# Arduino.net
KiCad netlist of a schematic drawn in EAGLE
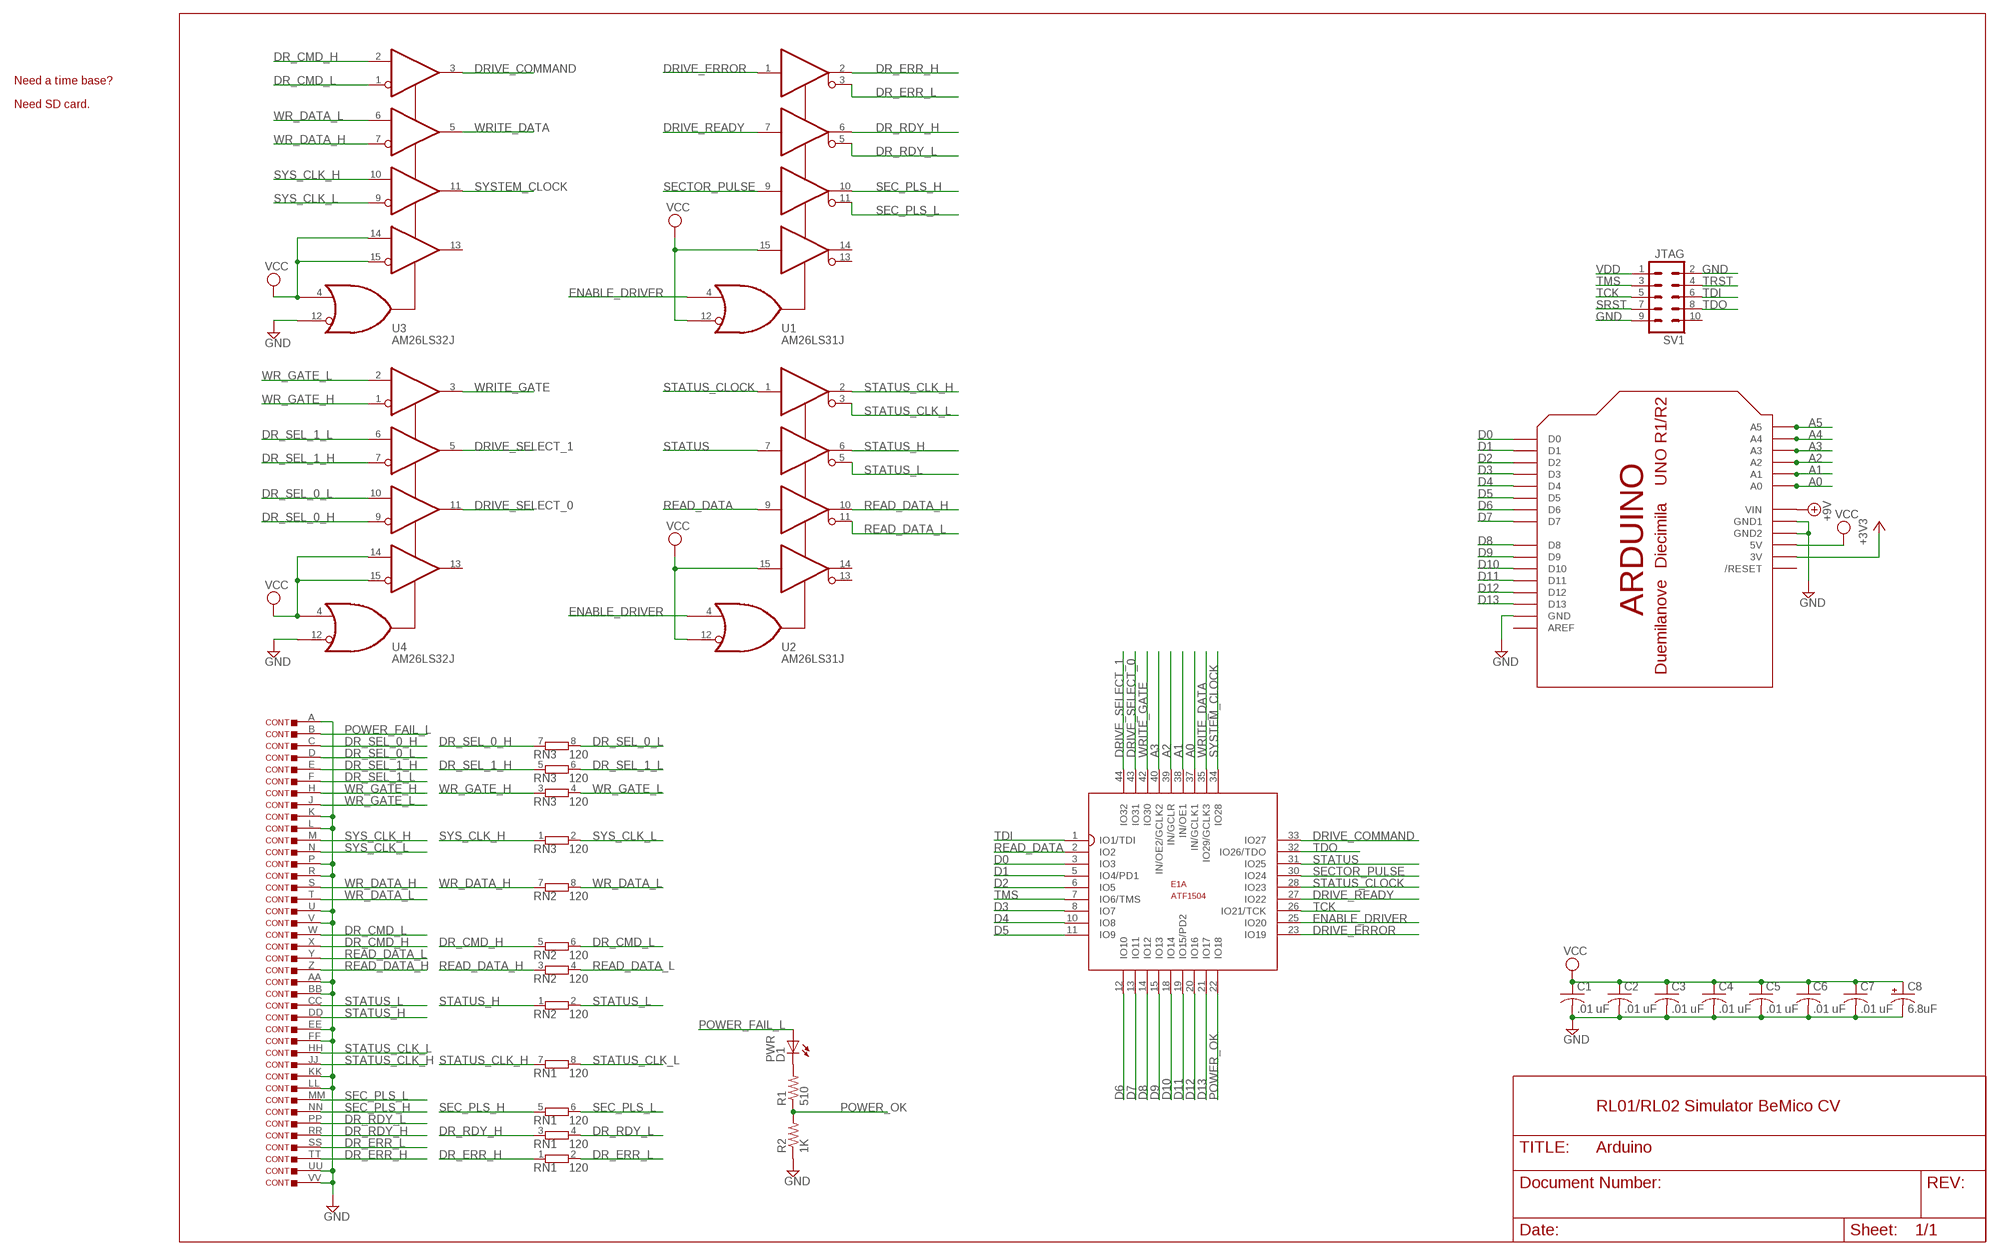
[diagram p0: schematic, sheet 1]

(export (version "E")
  (design (tool "Eeschema 10.0.6"))
  (components
    (comp (ref "C1")
      (value ".01 uF")
      (footprint "eagle-import:C050-025X075")
      (libsource (lib "eagle-import") (part "C-US050-025X075"))
    )
    (comp (ref "C2")
      (value ".01 uF")
      (footprint "eagle-import:C050-025X075")
      (libsource (lib "eagle-import") (part "C-US050-025X075"))
    )
    (comp (ref "C3")
      (value ".01 uF")
      (footprint "eagle-import:C050-025X075")
      (libsource (lib "eagle-import") (part "C-US050-025X075"))
    )
    (comp (ref "C4")
      (value ".01 uF")
      (footprint "eagle-import:C050-025X075")
      (libsource (lib "eagle-import") (part "C-US050-025X075"))
    )
    (comp (ref "C5")
      (value ".01 uF")
      (footprint "eagle-import:C050-025X075")
      (libsource (lib "eagle-import") (part "C-US050-025X075"))
    )
    (comp (ref "C6")
      (value ".01 uF")
      (footprint "eagle-import:C050-025X075")
      (libsource (lib "eagle-import") (part "C-US050-025X075"))
    )
    (comp (ref "C7")
      (value ".01 uF")
      (footprint "eagle-import:C050-025X075")
      (libsource (lib "eagle-import") (part "C-US050-025X075"))
    )
    (comp (ref "C8")
      (value "6.8uF")
      (footprint "eagle-import:E5-5")
      (libsource (lib "eagle-import") (part "CPOL-USE5-5"))
    )
    (comp (ref "CONT")
      (value "DEC40PINSV")
      (footprint "eagle-import:DEC40PINV")
      (libsource (lib "eagle-import") (part "DEC40PINSV"))
    )
    (comp (ref "D1")
      (value "PWR")
      (footprint "eagle-import:LED5MM")
      (libsource (lib "eagle-import") (part "LED5MM"))
    )
    (comp (ref "E1")
      (value "ATF1504")
      (footprint "eagle-import:TQFP44")
      (libsource (lib "eagle-import") (part "ATF150X44TQFP"))
    )
    (comp (ref "R1")
      (value "510")
      (footprint "eagle-import:0207_10")
      (libsource (lib "eagle-import") (part "R-US_0207/10"))
    )
    (comp (ref "R2")
      (value "1K")
      (footprint "eagle-import:0207_10")
      (libsource (lib "eagle-import") (part "R-US_0207/10"))
    )
    (comp (ref "RN1")
      (value "120")
      (footprint "eagle-import:SIL8")
      (libsource (lib "eagle-import") (part "E4RP"))
    )
    (comp (ref "RN2")
      (value "120")
      (footprint "eagle-import:SIL8")
      (libsource (lib "eagle-import") (part "E4RP"))
    )
    (comp (ref "RN3")
      (value "120")
      (footprint "eagle-import:SIL8")
      (libsource (lib "eagle-import") (part "E4RP"))
    )
    (comp (ref "SV1")
      (value "JTAG")
      (footprint "eagle-import:ML10")
      (libsource (lib "eagle-import") (part "ML10"))
    )
    (comp (ref "U$3")
      (value "ARDUINOUNO")
      (footprint "eagle-import:ARDUINO")
      (libsource (lib "eagle-import") (part "ARDUINOUNO"))
    )
    (comp (ref "U1")
      (value "AM26LS31J")
      (footprint "eagle-import:SO16")
      (libsource (lib "eagle-import") (part "AM26LS31J"))
    )
    (comp (ref "U2")
      (value "AM26LS31J")
      (footprint "eagle-import:SO16")
      (libsource (lib "eagle-import") (part "AM26LS31J"))
    )
    (comp (ref "U3")
      (value "AM26LS32J")
      (footprint "eagle-import:SO16")
      (libsource (lib "eagle-import") (part "AM26LS32J"))
    )
    (comp (ref "U4")
      (value "AM26LS32J")
      (footprint "eagle-import:SO16")
      (libsource (lib "eagle-import") (part "AM26LS32J"))
    )
  )
  (nets
    (net (code "1") (name "+3V3") (class "Default")
      (node (ref "U$3") (pin "3V") (pinfunction "3V_3V") (pintype "power_in"))
    )
    (net (code "2") (name "+9V") (class "Default")
      (node (ref "U$3") (pin "VIN") (pinfunction "VIN_VIN") (pintype "power_in"))
    )
    (net (code "3") (name "/A0") (class "Default")
      (node (ref "E1") (pin "37") (pinfunction "IN/GCLK1_37") (pintype "input"))
      (node (ref "U$3") (pin "A0") (pinfunction "A0_A0") (pintype "bidirectional"))
    )
    (net (code "4") (name "/A1") (class "Default")
      (node (ref "E1") (pin "38") (pinfunction "IN/OE1_38") (pintype "input"))
      (node (ref "U$3") (pin "A1") (pinfunction "A1_A1") (pintype "bidirectional"))
    )
    (net (code "5") (name "/A2") (class "Default")
      (node (ref "E1") (pin "39") (pinfunction "IN/GCLR_39") (pintype "input"))
      (node (ref "U$3") (pin "A2") (pinfunction "A2_A2") (pintype "bidirectional"))
    )
    (net (code "6") (name "/A3") (class "Default")
      (node (ref "E1") (pin "40") (pinfunction "IN/OE2/GCLK2_40") (pintype "input"))
      (node (ref "U$3") (pin "A3") (pinfunction "A3_A3") (pintype "bidirectional"))
    )
    (net (code "7") (name "/A4") (class "Default")
      (node (ref "U$3") (pin "A4") (pinfunction "A4_A4") (pintype "bidirectional"))
    )
    (net (code "8") (name "/A5") (class "Default")
      (node (ref "U$3") (pin "A5") (pinfunction "A5_A5") (pintype "bidirectional"))
    )
    (net (code "9") (name "/D0") (class "Default")
      (node (ref "E1") (pin "3") (pinfunction "IO3_3") (pintype "bidirectional"))
      (node (ref "U$3") (pin "D0") (pinfunction "D0_D0") (pintype "bidirectional"))
    )
    (net (code "10") (name "/D1") (class "Default")
      (node (ref "E1") (pin "5") (pinfunction "IO4/PD1_5") (pintype "bidirectional"))
      (node (ref "U$3") (pin "D1") (pinfunction "D1_D1") (pintype "bidirectional"))
    )
    (net (code "11") (name "/D2") (class "Default")
      (node (ref "E1") (pin "6") (pinfunction "IO5_6") (pintype "bidirectional"))
      (node (ref "U$3") (pin "D2") (pinfunction "D2_D2") (pintype "bidirectional"))
    )
    (net (code "12") (name "/D3") (class "Default")
      (node (ref "E1") (pin "8") (pinfunction "IO7_8") (pintype "bidirectional"))
      (node (ref "U$3") (pin "D3") (pinfunction "D3_D3") (pintype "bidirectional"))
    )
    (net (code "13") (name "/D4") (class "Default")
      (node (ref "E1") (pin "10") (pinfunction "IO8_10") (pintype "bidirectional"))
      (node (ref "U$3") (pin "D4") (pinfunction "D4_D4") (pintype "bidirectional"))
    )
    (net (code "14") (name "/D5") (class "Default")
      (node (ref "E1") (pin "11") (pinfunction "IO9_11") (pintype "bidirectional"))
      (node (ref "U$3") (pin "D5") (pinfunction "D5_D5") (pintype "bidirectional"))
    )
    (net (code "15") (name "/D6") (class "Default")
      (node (ref "E1") (pin "12") (pinfunction "IO10_12") (pintype "bidirectional"))
      (node (ref "U$3") (pin "D6") (pinfunction "D6_D6") (pintype "bidirectional"))
    )
    (net (code "16") (name "/D7") (class "Default")
      (node (ref "E1") (pin "13") (pinfunction "IO11_13") (pintype "bidirectional"))
      (node (ref "U$3") (pin "D7") (pinfunction "D7_D7") (pintype "bidirectional"))
    )
    (net (code "17") (name "/D8") (class "Default")
      (node (ref "E1") (pin "14") (pinfunction "IO12_14") (pintype "bidirectional"))
      (node (ref "U$3") (pin "D8") (pinfunction "D8_D8") (pintype "bidirectional"))
    )
    (net (code "18") (name "/D9") (class "Default")
      (node (ref "E1") (pin "15") (pinfunction "IO13_15") (pintype "bidirectional"))
      (node (ref "U$3") (pin "D9") (pinfunction "D9_D9") (pintype "bidirectional"))
    )
    (net (code "19") (name "/D10") (class "Default")
      (node (ref "E1") (pin "18") (pinfunction "IO14_18") (pintype "bidirectional"))
      (node (ref "U$3") (pin "D10") (pinfunction "D10_D10") (pintype "bidirectional"))
    )
    (net (code "20") (name "/D11") (class "Default")
      (node (ref "E1") (pin "19") (pinfunction "IO15/PD2_19") (pintype "bidirectional"))
      (node (ref "U$3") (pin "D11") (pinfunction "D11_D11") (pintype "bidirectional"))
    )
    (net (code "21") (name "/D12") (class "Default")
      (node (ref "E1") (pin "20") (pinfunction "IO16_20") (pintype "bidirectional"))
      (node (ref "U$3") (pin "D12") (pinfunction "D12_D12") (pintype "bidirectional"))
    )
    (net (code "22") (name "/D13") (class "Default")
      (node (ref "E1") (pin "21") (pinfunction "IO17_21") (pintype "bidirectional"))
      (node (ref "U$3") (pin "D13") (pinfunction "D13_D13") (pintype "bidirectional"))
    )
    (net (code "23") (name "/DRIVE_COMMAND") (class "Default")
      (node (ref "E1") (pin "33") (pinfunction "IO27_33") (pintype "bidirectional"))
      (node (ref "U3") (pin "3") (pinfunction "Y1_3") (pintype "output"))
    )
    (net (code "24") (name "/DRIVE_ERROR") (class "Default")
      (node (ref "E1") (pin "23") (pinfunction "IO19_23") (pintype "bidirectional"))
      (node (ref "U1") (pin "1") (pinfunction "A1_1") (pintype "input"))
    )
    (net (code "25") (name "/DRIVE_READY") (class "Default")
      (node (ref "E1") (pin "27") (pinfunction "IO22_27") (pintype "bidirectional"))
      (node (ref "U1") (pin "7") (pinfunction "A2_7") (pintype "input"))
    )
    (net (code "26") (name "/DRIVE_SELECT_0") (class "Default")
      (node (ref "E1") (pin "43") (pinfunction "IO31_43") (pintype "bidirectional"))
      (node (ref "U4") (pin "11") (pinfunction "Y3_11") (pintype "output"))
    )
    (net (code "27") (name "/DRIVE_SELECT_1") (class "Default")
      (node (ref "E1") (pin "44") (pinfunction "IO32_44") (pintype "bidirectional"))
      (node (ref "U4") (pin "5") (pinfunction "Y2_5") (pintype "output"))
    )
    (net (code "28") (name "/DR_CMD_H") (class "Default")
      (node (ref "CONT") (pin "X") (pinfunction "P$2_X") (pintype "passive"))
      (node (ref "RN2") (pin "5") (pinfunction "1_5") (pintype "passive"))
      (node (ref "U3") (pin "2") (pinfunction "P1_2") (pintype "input"))
    )
    (net (code "29") (name "/DR_CMD_L") (class "Default")
      (node (ref "CONT") (pin "W") (pinfunction "P$2_W") (pintype "passive"))
      (node (ref "RN2") (pin "6") (pinfunction "2_6") (pintype "passive"))
      (node (ref "U3") (pin "1") (pinfunction "N1_1") (pintype "input"))
    )
    (net (code "30") (name "/DR_ERR_H") (class "Default")
      (node (ref "CONT") (pin "TT") (pinfunction "P$2_TT") (pintype "passive"))
      (node (ref "RN1") (pin "1") (pinfunction "1_1") (pintype "passive"))
      (node (ref "U1") (pin "2") (pinfunction "Y1_2") (pintype "output"))
    )
    (net (code "31") (name "/DR_ERR_L") (class "Default")
      (node (ref "CONT") (pin "SS") (pinfunction "P$2_SS") (pintype "passive"))
      (node (ref "RN1") (pin "2") (pinfunction "2_2") (pintype "passive"))
      (node (ref "U1") (pin "3") (pinfunction "Z1_3") (pintype "output"))
    )
    (net (code "32") (name "/DR_RDY_H") (class "Default")
      (node (ref "CONT") (pin "RR") (pinfunction "P$2_RR") (pintype "passive"))
      (node (ref "RN1") (pin "3") (pinfunction "1_3") (pintype "passive"))
      (node (ref "U1") (pin "6") (pinfunction "Y2_6") (pintype "output"))
    )
    (net (code "33") (name "/DR_RDY_L") (class "Default")
      (node (ref "CONT") (pin "PP") (pinfunction "P$2_PP") (pintype "passive"))
      (node (ref "RN1") (pin "4") (pinfunction "2_4") (pintype "passive"))
      (node (ref "U1") (pin "5") (pinfunction "Z2_5") (pintype "output"))
    )
    (net (code "34") (name "/DR_SEL_0_H") (class "Default")
      (node (ref "CONT") (pin "C") (pinfunction "P$2_C") (pintype "passive"))
      (node (ref "RN3") (pin "7") (pinfunction "1_7") (pintype "passive"))
      (node (ref "U4") (pin "9") (pinfunction "N3_9") (pintype "input"))
    )
    (net (code "35") (name "/DR_SEL_0_L") (class "Default")
      (node (ref "CONT") (pin "D") (pinfunction "P$2_D") (pintype "passive"))
      (node (ref "RN3") (pin "8") (pinfunction "2_8") (pintype "passive"))
      (node (ref "U4") (pin "10") (pinfunction "P3_10") (pintype "input"))
    )
    (net (code "36") (name "/DR_SEL_1_H") (class "Default")
      (node (ref "CONT") (pin "E") (pinfunction "P$2_E") (pintype "passive"))
      (node (ref "RN3") (pin "5") (pinfunction "1_5") (pintype "passive"))
      (node (ref "U4") (pin "7") (pinfunction "N2_7") (pintype "input"))
    )
    (net (code "37") (name "/DR_SEL_1_L") (class "Default")
      (node (ref "CONT") (pin "F") (pinfunction "P$2_F") (pintype "passive"))
      (node (ref "RN3") (pin "6") (pinfunction "2_6") (pintype "passive"))
      (node (ref "U4") (pin "6") (pinfunction "P2_6") (pintype "input"))
    )
    (net (code "38") (name "/ENABLE_DRIVER") (class "Default")
      (node (ref "E1") (pin "25") (pinfunction "IO20_25") (pintype "bidirectional"))
      (node (ref "U1") (pin "4") (pinfunction "G_4") (pintype "input"))
      (node (ref "U2") (pin "4") (pinfunction "G_4") (pintype "input"))
    )
    (net (code "39") (name "/POWER_FAIL_L") (class "Default")
      (node (ref "CONT") (pin "B") (pinfunction "P$2_B") (pintype "passive"))
      (node (ref "D1") (pin "A") (pinfunction "A_A") (pintype "passive"))
    )
    (net (code "40") (name "/POWER_OK") (class "Default")
      (node (ref "E1") (pin "22") (pinfunction "IO18_22") (pintype "bidirectional"))
      (node (ref "R1") (pin "1") (pinfunction "1_1") (pintype "passive"))
      (node (ref "R2") (pin "2") (pinfunction "2_2") (pintype "passive"))
    )
    (net (code "41") (name "/READ_DATA") (class "Default")
      (node (ref "E1") (pin "2") (pinfunction "IO2_2") (pintype "bidirectional"))
      (node (ref "U2") (pin "9") (pinfunction "A3_9") (pintype "input"))
    )
    (net (code "42") (name "/READ_DATA_H") (class "Default")
      (node (ref "CONT") (pin "Z") (pinfunction "P$2_Z") (pintype "passive"))
      (node (ref "RN2") (pin "3") (pinfunction "1_3") (pintype "passive"))
      (node (ref "U2") (pin "10") (pinfunction "Y3_10") (pintype "output"))
    )
    (net (code "43") (name "/READ_DATA_L") (class "Default")
      (node (ref "CONT") (pin "Y") (pinfunction "P$2_Y") (pintype "passive"))
      (node (ref "RN2") (pin "4") (pinfunction "2_4") (pintype "passive"))
      (node (ref "U2") (pin "11") (pinfunction "Z3_11") (pintype "output"))
    )
    (net (code "44") (name "/SECTOR_PULSE") (class "Default")
      (node (ref "E1") (pin "30") (pinfunction "IO24_30") (pintype "bidirectional"))
      (node (ref "U1") (pin "9") (pinfunction "A3_9") (pintype "input"))
    )
    (net (code "45") (name "/SEC_PLS_H") (class "Default")
      (node (ref "CONT") (pin "NN") (pinfunction "P$2_NN") (pintype "passive"))
      (node (ref "RN1") (pin "5") (pinfunction "1_5") (pintype "passive"))
      (node (ref "U1") (pin "10") (pinfunction "Y3_10") (pintype "output"))
    )
    (net (code "46") (name "/SEC_PLS_L") (class "Default")
      (node (ref "CONT") (pin "MM") (pinfunction "P$2_MM") (pintype "passive"))
      (node (ref "RN1") (pin "6") (pinfunction "2_6") (pintype "passive"))
      (node (ref "U1") (pin "11") (pinfunction "Z3_11") (pintype "output"))
    )
    (net (code "47") (name "/SRST") (class "Default")
      (node (ref "SV1") (pin "7") (pinfunction "7_7") (pintype "passive"))
    )
    (net (code "48") (name "/STATUS") (class "Default")
      (node (ref "E1") (pin "31") (pinfunction "IO25_31") (pintype "bidirectional"))
      (node (ref "U2") (pin "7") (pinfunction "A2_7") (pintype "input"))
    )
    (net (code "49") (name "/STATUS_CLK_H") (class "Default")
      (node (ref "CONT") (pin "JJ") (pinfunction "P$2_JJ") (pintype "passive"))
      (node (ref "RN1") (pin "7") (pinfunction "1_7") (pintype "passive"))
      (node (ref "U2") (pin "2") (pinfunction "Y1_2") (pintype "output"))
    )
    (net (code "50") (name "/STATUS_CLK_L") (class "Default")
      (node (ref "CONT") (pin "HH") (pinfunction "P$2_HH") (pintype "passive"))
      (node (ref "RN1") (pin "8") (pinfunction "2_8") (pintype "passive"))
      (node (ref "U2") (pin "3") (pinfunction "Z1_3") (pintype "output"))
    )
    (net (code "51") (name "/STATUS_CLOCK") (class "Default")
      (node (ref "E1") (pin "28") (pinfunction "IO23_28") (pintype "bidirectional"))
      (node (ref "U2") (pin "1") (pinfunction "A1_1") (pintype "input"))
    )
    (net (code "52") (name "/STATUS_H") (class "Default")
      (node (ref "CONT") (pin "DD") (pinfunction "P$2_DD") (pintype "passive"))
      (node (ref "RN2") (pin "1") (pinfunction "1_1") (pintype "passive"))
      (node (ref "U2") (pin "6") (pinfunction "Y2_6") (pintype "output"))
    )
    (net (code "53") (name "/STATUS_L") (class "Default")
      (node (ref "CONT") (pin "CC") (pinfunction "P$2_CC") (pintype "passive"))
      (node (ref "RN2") (pin "2") (pinfunction "2_2") (pintype "passive"))
      (node (ref "U2") (pin "5") (pinfunction "Z2_5") (pintype "output"))
    )
    (net (code "54") (name "/SYSTEM_CLOCK") (class "Default")
      (node (ref "E1") (pin "34") (pinfunction "IO28_34") (pintype "bidirectional"))
      (node (ref "U3") (pin "11") (pinfunction "Y3_11") (pintype "output"))
    )
    (net (code "55") (name "/SYS_CLK_H") (class "Default")
      (node (ref "CONT") (pin "M") (pinfunction "P$2_M") (pintype "passive"))
      (node (ref "RN3") (pin "1") (pinfunction "1_1") (pintype "passive"))
      (node (ref "U3") (pin "10") (pinfunction "P3_10") (pintype "input"))
    )
    (net (code "56") (name "/SYS_CLK_L") (class "Default")
      (node (ref "CONT") (pin "N") (pinfunction "P$2_N") (pintype "passive"))
      (node (ref "RN3") (pin "2") (pinfunction "2_2") (pintype "passive"))
      (node (ref "U3") (pin "9") (pinfunction "N3_9") (pintype "input"))
    )
    (net (code "57") (name "/TCK") (class "Default")
      (node (ref "E1") (pin "26") (pinfunction "IO21/TCK_26") (pintype "bidirectional"))
      (node (ref "SV1") (pin "5") (pinfunction "5_5") (pintype "passive"))
    )
    (net (code "58") (name "/TDI") (class "Default")
      (node (ref "E1") (pin "1") (pinfunction "IO1/TDI_1") (pintype "bidirectional"))
      (node (ref "SV1") (pin "6") (pinfunction "6_6") (pintype "passive"))
    )
    (net (code "59") (name "/TDO") (class "Default")
      (node (ref "E1") (pin "32") (pinfunction "IO26/TDO_32") (pintype "bidirectional"))
      (node (ref "SV1") (pin "8") (pinfunction "8_8") (pintype "passive"))
    )
    (net (code "60") (name "/TMS") (class "Default")
      (node (ref "E1") (pin "7") (pinfunction "IO6/TMS_7") (pintype "bidirectional"))
      (node (ref "SV1") (pin "3") (pinfunction "3_3") (pintype "passive"))
    )
    (net (code "61") (name "/TRST") (class "Default")
      (node (ref "SV1") (pin "4") (pinfunction "4_4") (pintype "passive"))
    )
    (net (code "62") (name "/VDD") (class "Default")
      (node (ref "SV1") (pin "1") (pinfunction "1_1") (pintype "passive"))
    )
    (net (code "63") (name "/WRITE_DATA") (class "Default")
      (node (ref "E1") (pin "35") (pinfunction "IO29/GCLK3_35") (pintype "bidirectional"))
      (node (ref "U3") (pin "5") (pinfunction "Y2_5") (pintype "output"))
    )
    (net (code "64") (name "/WRITE_GATE") (class "Default")
      (node (ref "E1") (pin "42") (pinfunction "IO30_42") (pintype "bidirectional"))
      (node (ref "U4") (pin "3") (pinfunction "Y1_3") (pintype "output"))
    )
    (net (code "65") (name "/WR_DATA_H") (class "Default")
      (node (ref "CONT") (pin "S") (pinfunction "P$2_S") (pintype "passive"))
      (node (ref "RN2") (pin "7") (pinfunction "1_7") (pintype "passive"))
      (node (ref "U3") (pin "7") (pinfunction "N2_7") (pintype "input"))
    )
    (net (code "66") (name "/WR_DATA_L") (class "Default")
      (node (ref "CONT") (pin "T") (pinfunction "P$2_T") (pintype "passive"))
      (node (ref "RN2") (pin "8") (pinfunction "2_8") (pintype "passive"))
      (node (ref "U3") (pin "6") (pinfunction "P2_6") (pintype "input"))
    )
    (net (code "67") (name "/WR_GATE_H") (class "Default")
      (node (ref "CONT") (pin "H") (pinfunction "P$2_H") (pintype "passive"))
      (node (ref "RN3") (pin "3") (pinfunction "1_3") (pintype "passive"))
      (node (ref "U4") (pin "1") (pinfunction "N1_1") (pintype "input"))
    )
    (net (code "68") (name "/WR_GATE_L") (class "Default")
      (node (ref "CONT") (pin "J") (pinfunction "P$2_J") (pintype "passive"))
      (node (ref "RN3") (pin "4") (pinfunction "2_4") (pintype "passive"))
      (node (ref "U4") (pin "2") (pinfunction "P1_2") (pintype "input"))
    )
    (net (code "69") (name "GND") (class "Default")
      (node (ref "C1") (pin "2") (pinfunction "2_2") (pintype "passive"))
      (node (ref "C2") (pin "2") (pinfunction "2_2") (pintype "passive"))
      (node (ref "C3") (pin "2") (pinfunction "2_2") (pintype "passive"))
      (node (ref "C4") (pin "2") (pinfunction "2_2") (pintype "passive"))
      (node (ref "C5") (pin "2") (pinfunction "2_2") (pintype "passive"))
      (node (ref "C6") (pin "2") (pinfunction "2_2") (pintype "passive"))
      (node (ref "C7") (pin "2") (pinfunction "2_2") (pintype "passive"))
      (node (ref "C8") (pin "-") (pinfunction "-_-") (pintype "passive"))
      (node (ref "CONT") (pin "A") (pinfunction "P$2_A") (pintype "passive"))
      (node (ref "CONT") (pin "AA") (pinfunction "P$2_AA") (pintype "passive"))
      (node (ref "CONT") (pin "BB") (pinfunction "P$2_BB") (pintype "passive"))
      (node (ref "CONT") (pin "EE") (pinfunction "P$2_EE") (pintype "passive"))
      (node (ref "CONT") (pin "FF") (pinfunction "P$2_FF") (pintype "passive"))
      (node (ref "CONT") (pin "K") (pinfunction "P$2_K") (pintype "passive"))
      (node (ref "CONT") (pin "KK") (pinfunction "P$2_KK") (pintype "passive"))
      (node (ref "CONT") (pin "L") (pinfunction "P$2_L") (pintype "passive"))
      (node (ref "CONT") (pin "LL") (pinfunction "P$2_LL") (pintype "passive"))
      (node (ref "CONT") (pin "P") (pinfunction "P$2_P") (pintype "passive"))
      (node (ref "CONT") (pin "R") (pinfunction "P$2_R") (pintype "passive"))
      (node (ref "CONT") (pin "U") (pinfunction "P$2_U") (pintype "passive"))
      (node (ref "CONT") (pin "UU") (pinfunction "P$2_UU") (pintype "passive"))
      (node (ref "CONT") (pin "V") (pinfunction "P$2_V") (pintype "passive"))
      (node (ref "CONT") (pin "VV") (pinfunction "P$2_VV") (pintype "passive"))
      (node (ref "R2") (pin "1") (pinfunction "1_1") (pintype "passive"))
      (node (ref "SV1") (pin "2") (pinfunction "2_2") (pintype "passive"))
      (node (ref "SV1") (pin "9") (pinfunction "9_9") (pintype "passive"))
      (node (ref "U$3") (pin "GND") (pinfunction "GND_GND") (pintype "power_in"))
      (node (ref "U$3") (pin "GND1") (pinfunction "GND1_GND1") (pintype "power_in"))
      (node (ref "U$3") (pin "GND2") (pinfunction "GND2_GND2") (pintype "power_in"))
      (node (ref "U3") (pin "12") (pinfunction "~{G}_12") (pintype "input"))
      (node (ref "U4") (pin "12") (pinfunction "~{G}_12") (pintype "input"))
    )
    (net (code "70") (name "Net-(D1-C)") (class "Default")
      (node (ref "D1") (pin "K") (pinfunction "C_K") (pintype "passive"))
      (node (ref "R1") (pin "2") (pinfunction "2_2") (pintype "passive"))
    )
    (net (code "71") (name "VCC") (class "Default")
      (node (ref "C1") (pin "1") (pinfunction "1_1") (pintype "passive"))
      (node (ref "C2") (pin "1") (pinfunction "1_1") (pintype "passive"))
      (node (ref "C3") (pin "1") (pinfunction "1_1") (pintype "passive"))
      (node (ref "C4") (pin "1") (pinfunction "1_1") (pintype "passive"))
      (node (ref "C5") (pin "1") (pinfunction "1_1") (pintype "passive"))
      (node (ref "C6") (pin "1") (pinfunction "1_1") (pintype "passive"))
      (node (ref "C7") (pin "1") (pinfunction "1_1") (pintype "passive"))
      (node (ref "C8") (pin "+") (pinfunction "+_+") (pintype "passive"))
      (node (ref "U$3") (pin "5V") (pinfunction "5V_5V") (pintype "power_in"))
      (node (ref "U1") (pin "12") (pinfunction "~{G}_12") (pintype "input"))
      (node (ref "U1") (pin "15") (pinfunction "A4_15") (pintype "input"))
      (node (ref "U2") (pin "12") (pinfunction "~{G}_12") (pintype "input"))
      (node (ref "U2") (pin "15") (pinfunction "A4_15") (pintype "input"))
      (node (ref "U3") (pin "14") (pinfunction "P4_14") (pintype "input"))
      (node (ref "U3") (pin "15") (pinfunction "N4_15") (pintype "input"))
      (node (ref "U3") (pin "4") (pinfunction "G_4") (pintype "input"))
      (node (ref "U4") (pin "14") (pinfunction "P4_14") (pintype "input"))
      (node (ref "U4") (pin "15") (pinfunction "N4_15") (pintype "input"))
      (node (ref "U4") (pin "4") (pinfunction "G_4") (pintype "input"))
    )
    (net (code "72") (name "unconnected-(SV1-Pad10)") (class "Default")
      (node (ref "SV1") (pin "10") (pinfunction "10_10") (pintype "passive"))
    )
    (net (code "73") (name "unconnected-(U$3-PadAREF)") (class "Default")
      (node (ref "U$3") (pin "AREF") (pinfunction "AREF_AREF") (pintype "bidirectional"))
    )
    (net (code "74") (name "unconnected-(U$3-{slash}RESET-PadRESET)") (class "Default")
      (node (ref "U$3") (pin "RESET") (pinfunction "/RESET_RESET") (pintype "bidirectional"))
    )
    (net (code "75") (name "unconnected-(U1A-Y4-Pad14)") (class "Default")
      (node (ref "U1") (pin "14") (pinfunction "Y4_14") (pintype "output"))
    )
    (net (code "76") (name "unconnected-(U1A-Z4-Pad13)") (class "Default")
      (node (ref "U1") (pin "13") (pinfunction "Z4_13") (pintype "output"))
    )
    (net (code "77") (name "unconnected-(U2A-Y4-Pad14)") (class "Default")
      (node (ref "U2") (pin "14") (pinfunction "Y4_14") (pintype "output"))
    )
    (net (code "78") (name "unconnected-(U2A-Z4-Pad13)") (class "Default")
      (node (ref "U2") (pin "13") (pinfunction "Z4_13") (pintype "output"))
    )
    (net (code "79") (name "unconnected-(U3A-Y4-Pad13)") (class "Default")
      (node (ref "U3") (pin "13") (pinfunction "Y4_13") (pintype "output"))
    )
    (net (code "80") (name "unconnected-(U4A-Y4-Pad13)") (class "Default")
      (node (ref "U4") (pin "13") (pinfunction "Y4_13") (pintype "output"))
    )
  )
)
